# filtroBA.net
KiCad netlist of a schematic drawn in Altium Designer
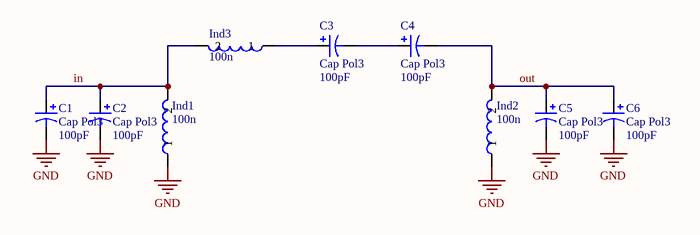
[diagram p0: filtroBA.SchDoc]

(export (version "E")
  (design (tool "Eeschema 10.0.6"))
  (components
    (comp (ref "C1")
      (value "Cap Pol3")
      (footprint "C0805")
      (description "Polarized Capacitor (Surface Mount)")
      (fields (field (name "ALTIUM_VALUE") "100pF") (field (name "PUBLISHER") "Altium Limited"))
      (libsource (lib "Miscellaneous Devices") (part "Cap Pol3"))
    )
    (comp (ref "C2")
      (value "Cap Pol3")
      (footprint "C0805")
      (description "Polarized Capacitor (Surface Mount)")
      (fields (field (name "ALTIUM_VALUE") "100pF") (field (name "PUBLISHER") "Altium Limited"))
      (libsource (lib "Miscellaneous Devices") (part "Cap Pol3"))
    )
    (comp (ref "C3")
      (value "Cap Pol3")
      (footprint "C0805")
      (description "Polarized Capacitor (Surface Mount)")
      (fields (field (name "ALTIUM_VALUE") "100pF") (field (name "PUBLISHER") "Altium Limited"))
      (libsource (lib "Miscellaneous Devices") (part "Cap Pol3"))
    )
    (comp (ref "C4")
      (value "Cap Pol3")
      (footprint "C0805")
      (description "Polarized Capacitor (Surface Mount)")
      (fields (field (name "ALTIUM_VALUE") "100pF") (field (name "PUBLISHER") "Altium Limited"))
      (libsource (lib "Miscellaneous Devices") (part "Cap Pol3"))
    )
    (comp (ref "C5")
      (value "Cap Pol3")
      (footprint "C0805")
      (description "Polarized Capacitor (Surface Mount)")
      (fields (field (name "ALTIUM_VALUE") "100pF") (field (name "PUBLISHER") "Altium Limited"))
      (libsource (lib "Miscellaneous Devices") (part "Cap Pol3"))
    )
    (comp (ref "C6")
      (value "Cap Pol3")
      (footprint "C0805")
      (description "Polarized Capacitor (Surface Mount)")
      (fields (field (name "ALTIUM_VALUE") "100pF") (field (name "PUBLISHER") "Altium Limited"))
      (libsource (lib "Miscellaneous Devices") (part "Cap Pol3"))
    )
    (comp (ref "Ind1")
      (value "Ind2")
      (footprint "Ind_3mm")
      (fields (field (name "VALOR") "100n"))
      (libsource (lib "epf") (part "Ind2"))
    )
    (comp (ref "Ind2")
      (value "Ind2")
      (footprint "Ind_3mm")
      (fields (field (name "VALOR") "100n"))
      (libsource (lib "epf") (part "Ind2"))
    )
    (comp (ref "Ind3")
      (value "Ind2")
      (footprint "IND_7MM")
      (fields (field (name "VALOR") "100n"))
      (libsource (lib "epf") (part "Ind2"))
    )
  )
  (nets
    (net (code "1") (name "/in") (class "Default")
      (node (ref "C1") (pin "1") (pinfunction "1_1") (pintype "passive"))
      (node (ref "C2") (pin "1") (pinfunction "1_1") (pintype "passive"))
      (node (ref "Ind1") (pin "2") (pinfunction "2_2") (pintype "passive"))
      (node (ref "Ind3") (pin "2") (pinfunction "2_2") (pintype "passive"))
    )
    (net (code "2") (name "/out") (class "Default")
      (node (ref "C4") (pin "2") (pinfunction "2_2") (pintype "passive"))
      (node (ref "C5") (pin "1") (pinfunction "1_1") (pintype "passive"))
      (node (ref "C6") (pin "1") (pinfunction "1_1") (pintype "passive"))
      (node (ref "Ind2") (pin "2") (pinfunction "2_2") (pintype "passive"))
    )
    (net (code "3") (name "GND") (class "Default")
      (node (ref "C1") (pin "2") (pinfunction "2_2") (pintype "passive"))
      (node (ref "C2") (pin "2") (pinfunction "2_2") (pintype "passive"))
      (node (ref "C5") (pin "2") (pinfunction "2_2") (pintype "passive"))
      (node (ref "C6") (pin "2") (pinfunction "2_2") (pintype "passive"))
      (node (ref "Ind1") (pin "1") (pinfunction "1_1") (pintype "passive"))
      (node (ref "Ind2") (pin "1") (pinfunction "1_1") (pintype "passive"))
    )
    (net (code "4") (name "Net-(C3-Pad1)") (class "Default")
      (node (ref "C3") (pin "1") (pinfunction "1_1") (pintype "passive"))
      (node (ref "Ind3") (pin "1") (pinfunction "1_1") (pintype "passive"))
    )
    (net (code "5") (name "Net-(C3-Pad2)") (class "Default")
      (node (ref "C3") (pin "2") (pinfunction "2_2") (pintype "passive"))
      (node (ref "C4") (pin "1") (pinfunction "1_1") (pintype "passive"))
    )
  )
)
